# ne555_ht.net
KiCad netlist of a schematic drawn in EAGLE
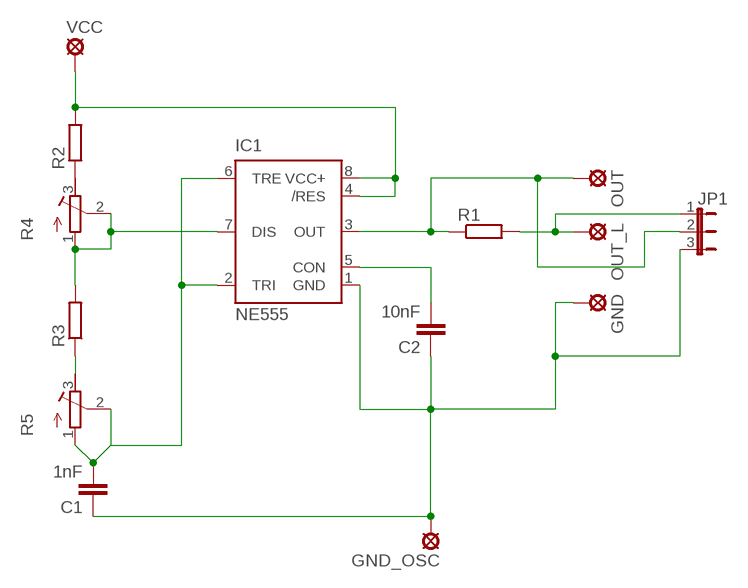
[diagram p0: schematic, sheet 1]

(export (version "E")
  (design (tool "Eeschema 10.0.6"))
  (components
    (comp (ref "C1")
      (value "1nF")
      (footprint "eagle-import:C050-024X044")
      (libsource (lib "eagle-import") (part "C-EU050-024X044"))
    )
    (comp (ref "C2")
      (value "10nF")
      (footprint "eagle-import:C050-024X044")
      (libsource (lib "eagle-import") (part "C-EU050-024X044"))
    )
    (comp (ref "GND")
      (value "LSP13")
      (footprint "eagle-import:LSP13")
      (libsource (lib "eagle-import") (part "LSP13"))
    )
    (comp (ref "GND_OSC")
      (value "LSP13")
      (footprint "eagle-import:LSP13")
      (libsource (lib "eagle-import") (part "LSP13"))
    )
    (comp (ref "IC1")
      (value "NE555")
      (footprint "eagle-import:DIL-08")
      (fields (field (name "MF") "Arrow Electronics") (field (name "MPN") "NE555N"))
      (libsource (lib "eagle-import") (part "NE555"))
    )
    (comp (ref "JP1")
      (value "JP2E")
      (footprint "eagle-import:JP2")
      (libsource (lib "eagle-import") (part "JP2E"))
    )
    (comp (ref "OUT")
      (value "LSP13")
      (footprint "eagle-import:LSP13")
      (libsource (lib "eagle-import") (part "LSP13"))
    )
    (comp (ref "OUT_L")
      (value "LSP13")
      (footprint "eagle-import:LSP13")
      (libsource (lib "eagle-import") (part "LSP13"))
    )
    (comp (ref "R1")
      (value "R-EU_0207/10")
      (footprint "eagle-import:0207_10")
      (libsource (lib "eagle-import") (part "resistor_R-EU_0207/10"))
    )
    (comp (ref "R2")
      (value "R-EU_0207/12")
      (footprint "eagle-import:0207_12")
      (libsource (lib "eagle-import") (part "R-EU_0207/12"))
    )
    (comp (ref "R3")
      (value "R-EU_0207/12")
      (footprint "eagle-import:0207_12")
      (libsource (lib "eagle-import") (part "R-EU_0207/12"))
    )
    (comp (ref "R4")
      (value "R-TRIMM3339P")
      (footprint "eagle-import:RTRIM3339P")
      (libsource (lib "eagle-import") (part "R-TRIMM3339P"))
    )
    (comp (ref "R5")
      (value "R-TRIMM3339P")
      (footprint "eagle-import:RTRIM3339P")
      (libsource (lib "eagle-import") (part "R-TRIMM3339P"))
    )
    (comp (ref "VCC")
      (value "LSP13")
      (footprint "eagle-import:LSP13")
      (libsource (lib "eagle-import") (part "LSP13"))
    )
  )
  (nets
    (net (code "1") (name "Net-(IC1-CON)") (class "Default")
      (node (ref "C2") (pin "2") (pinfunction "2_2") (pintype "passive"))
      (node (ref "IC1") (pin "5") (pinfunction "CON_5") (pintype "input"))
    )
    (net (code "2") (name "Net-(IC1-DIS)") (class "Default")
      (node (ref "IC1") (pin "7") (pinfunction "DIS_7") (pintype "input"))
      (node (ref "R3") (pin "2") (pinfunction "2_2") (pintype "passive"))
      (node (ref "R4") (pin "1") (pinfunction "A_1") (pintype "passive"))
      (node (ref "R4") (pin "2") (pinfunction "S_2") (pintype "passive"))
    )
    (net (code "3") (name "Net-(IC1-GND)") (class "Default")
      (node (ref "C1") (pin "1") (pinfunction "1_1") (pintype "passive"))
      (node (ref "C2") (pin "1") (pinfunction "1_1") (pintype "passive"))
      (node (ref "GND") (pin "MP") (pinfunction "MP_MP") (pintype "passive"))
      (node (ref "GND_OSC") (pin "MP") (pinfunction "MP_MP") (pintype "passive"))
      (node (ref "IC1") (pin "1") (pinfunction "GND_1") (pintype "power_in"))
      (node (ref "JP1") (pin "3") (pinfunction "3_3") (pintype "passive"))
    )
    (net (code "4") (name "Net-(IC1-OUT)") (class "Default")
      (node (ref "IC1") (pin "3") (pinfunction "OUT_3") (pintype "output"))
      (node (ref "JP1") (pin "2") (pinfunction "2_2") (pintype "passive"))
      (node (ref "OUT") (pin "MP") (pinfunction "MP_MP") (pintype "passive"))
      (node (ref "R1") (pin "1") (pinfunction "1_1") (pintype "passive"))
    )
    (net (code "5") (name "Net-(IC1-TRE)") (class "Default")
      (node (ref "C1") (pin "2") (pinfunction "2_2") (pintype "passive"))
      (node (ref "IC1") (pin "2") (pinfunction "TRI_2") (pintype "input"))
      (node (ref "IC1") (pin "6") (pinfunction "TRE_6") (pintype "input"))
      (node (ref "R5") (pin "1") (pinfunction "A_1") (pintype "passive"))
      (node (ref "R5") (pin "2") (pinfunction "S_2") (pintype "passive"))
    )
    (net (code "6") (name "Net-(IC1-VCC+)") (class "Default")
      (node (ref "IC1") (pin "4") (pinfunction "/RES_4") (pintype "input"))
      (node (ref "IC1") (pin "8") (pinfunction "VCC+_8") (pintype "power_in"))
      (node (ref "R2") (pin "2") (pinfunction "2_2") (pintype "passive"))
      (node (ref "VCC") (pin "MP") (pinfunction "MP_MP") (pintype "passive"))
    )
    (net (code "7") (name "Net-(JP1-Pad1)") (class "Default")
      (node (ref "JP1") (pin "1") (pinfunction "1_1") (pintype "passive"))
      (node (ref "OUT_L") (pin "MP") (pinfunction "MP_MP") (pintype "passive"))
      (node (ref "R1") (pin "2") (pinfunction "2_2") (pintype "passive"))
    )
    (net (code "8") (name "Net-(R4-E)") (class "Default")
      (node (ref "R2") (pin "1") (pinfunction "1_1") (pintype "passive"))
      (node (ref "R4") (pin "3") (pinfunction "E_3") (pintype "passive"))
    )
    (net (code "9") (name "Net-(R5-E)") (class "Default")
      (node (ref "R3") (pin "1") (pinfunction "1_1") (pintype "passive"))
      (node (ref "R5") (pin "3") (pinfunction "E_3") (pintype "passive"))
    )
  )
)
